# mainboard_motor_v1_3.net
KiCad netlist of a schematic drawn in Altium Designer
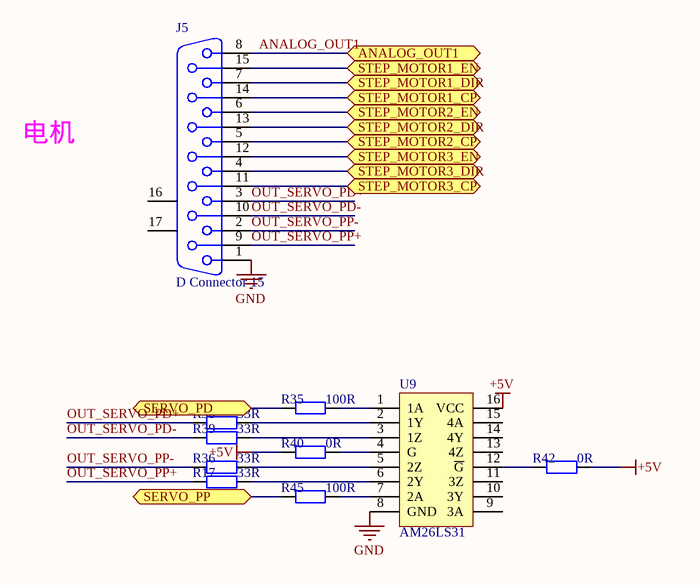
[diagram p0: mainboard_motor.v1.3.SchDoc]

(export (version "E")
  (design (tool "Eeschema 10.0.6"))
  (components
    (comp (ref "J5")
      (value "D Connector 15")
      (footprint "DSUB1.385-2H15")
      (description "Receptacle Assembly, 15 Position, Right Angle")
      (fields (field (name "PUBLISHER") "Altium Limited"))
      (libsource (lib "Miscellaneous Connectors") (part "D Connector 15"))
    )
    (comp (ref "R17")
      (value "33R")
      (footprint "0805")
      (description "Resistor")
      (fields (field (name "PUBLISHER") "Altium Limited"))
      (libsource (lib "TIAN's Schlib") (part "Res2"))
    )
    (comp (ref "R35")
      (value "100R")
      (footprint "0805")
      (description "Resistor")
      (fields (field (name "PUBLISHER") "Altium Limited"))
      (libsource (lib "TIAN's Schlib") (part "Res2"))
    )
    (comp (ref "R36")
      (value "33R")
      (footprint "0805")
      (description "Resistor")
      (fields (field (name "PUBLISHER") "Altium Limited"))
      (libsource (lib "TIAN's Schlib") (part "Res2"))
    )
    (comp (ref "R38")
      (value "33R")
      (footprint "0805")
      (description "Resistor")
      (fields (field (name "PUBLISHER") "Altium Limited"))
      (libsource (lib "TIAN's Schlib") (part "Res2"))
    )
    (comp (ref "R39")
      (value "33R")
      (footprint "0805")
      (description "Resistor")
      (fields (field (name "PUBLISHER") "Altium Limited"))
      (libsource (lib "TIAN's Schlib") (part "Res2"))
    )
    (comp (ref "R40")
      (value "0R")
      (footprint "0805")
      (description "Resistor")
      (fields (field (name "PUBLISHER") "Altium Limited"))
      (libsource (lib "TIAN's Schlib") (part "Res2"))
    )
    (comp (ref "R42")
      (value "0R")
      (footprint "0805")
      (description "Resistor")
      (fields (field (name "PUBLISHER") "Altium Limited"))
      (libsource (lib "TIAN's Schlib") (part "Res2"))
    )
    (comp (ref "R45")
      (value "100R")
      (footprint "0805")
      (description "Resistor")
      (fields (field (name "PUBLISHER") "Altium Limited"))
      (libsource (lib "TIAN's Schlib") (part "Res2"))
    )
    (comp (ref "U9") (value "AM26LS31") (footprint "SO-16") (libsource (lib "Chip") (part "AM26LS31")))
  )
  (nets
    (net (code "1") (name "+5V") (class "Default")
      (node (ref "R40") (pin "2") (pinfunction "2_2") (pintype "passive"))
      (node (ref "R42") (pin "1") (pinfunction "1_1") (pintype "passive"))
      (node (ref "U9") (pin "16") (pinfunction "VCC_16") (pintype "passive"))
    )
    (net (code "2") (name "/ANALOG_OUT1") (class "Default")
      (node (ref "J5") (pin "8") (pinfunction "8_8") (pintype "passive"))
    )
    (net (code "3") (name "/OUT_SERVO_PD+") (class "Default")
      (node (ref "J5") (pin "3") (pinfunction "3_3") (pintype "passive"))
      (node (ref "R38") (pin "2") (pinfunction "2_2") (pintype "passive"))
    )
    (net (code "4") (name "/OUT_SERVO_PD-") (class "Default")
      (node (ref "J5") (pin "10") (pinfunction "10_10") (pintype "passive"))
      (node (ref "R39") (pin "2") (pinfunction "2_2") (pintype "passive"))
    )
    (net (code "5") (name "/OUT_SERVO_PP+") (class "Default")
      (node (ref "J5") (pin "9") (pinfunction "9_9") (pintype "passive"))
      (node (ref "R17") (pin "2") (pinfunction "2_2") (pintype "passive"))
    )
    (net (code "6") (name "/OUT_SERVO_PP-") (class "Default")
      (node (ref "J5") (pin "2") (pinfunction "2_2") (pintype "passive"))
      (node (ref "R36") (pin "2") (pinfunction "2_2") (pintype "passive"))
    )
    (net (code "7") (name "/SERVO_PD") (class "Default")
      (node (ref "R35") (pin "2") (pinfunction "2_2") (pintype "passive"))
    )
    (net (code "8") (name "/SERVO_PP") (class "Default")
      (node (ref "R45") (pin "2") (pinfunction "2_2") (pintype "passive"))
    )
    (net (code "9") (name "/STEP_MOTOR1_CP") (class "Default")
      (node (ref "J5") (pin "14") (pinfunction "14_14") (pintype "passive"))
    )
    (net (code "10") (name "/STEP_MOTOR1_DIR") (class "Default")
      (node (ref "J5") (pin "7") (pinfunction "7_7") (pintype "passive"))
    )
    (net (code "11") (name "/STEP_MOTOR1_EN") (class "Default")
      (node (ref "J5") (pin "15") (pinfunction "15_15") (pintype "passive"))
    )
    (net (code "12") (name "/STEP_MOTOR2_CP") (class "Default")
      (node (ref "J5") (pin "5") (pinfunction "5_5") (pintype "passive"))
    )
    (net (code "13") (name "/STEP_MOTOR2_DIR") (class "Default")
      (node (ref "J5") (pin "13") (pinfunction "13_13") (pintype "passive"))
    )
    (net (code "14") (name "/STEP_MOTOR2_EN") (class "Default")
      (node (ref "J5") (pin "6") (pinfunction "6_6") (pintype "passive"))
    )
    (net (code "15") (name "/STEP_MOTOR3_CP") (class "Default")
      (node (ref "J5") (pin "11") (pinfunction "11_11") (pintype "passive"))
    )
    (net (code "16") (name "/STEP_MOTOR3_DIR") (class "Default")
      (node (ref "J5") (pin "4") (pinfunction "4_4") (pintype "passive"))
    )
    (net (code "17") (name "/STEP_MOTOR3_EN") (class "Default")
      (node (ref "J5") (pin "12") (pinfunction "12_12") (pintype "passive"))
    )
    (net (code "18") (name "GND") (class "Default")
      (node (ref "J5") (pin "1") (pinfunction "1_1") (pintype "passive"))
      (node (ref "U9") (pin "8") (pinfunction "GND_8") (pintype "passive"))
    )
    (net (code "19") (name "Net-(U9-1A)") (class "Default")
      (node (ref "R35") (pin "1") (pinfunction "1_1") (pintype "passive"))
      (node (ref "U9") (pin "1") (pinfunction "1A_1") (pintype "passive"))
    )
    (net (code "20") (name "Net-(U9-1Y)") (class "Default")
      (node (ref "R38") (pin "1") (pinfunction "1_1") (pintype "passive"))
      (node (ref "U9") (pin "2") (pinfunction "1Y_2") (pintype "passive"))
    )
    (net (code "21") (name "Net-(U9-1Z)") (class "Default")
      (node (ref "R39") (pin "1") (pinfunction "1_1") (pintype "passive"))
      (node (ref "U9") (pin "3") (pinfunction "1Z_3") (pintype "passive"))
    )
    (net (code "22") (name "Net-(U9-2A)") (class "Default")
      (node (ref "R45") (pin "1") (pinfunction "1_1") (pintype "passive"))
      (node (ref "U9") (pin "7") (pinfunction "2A_7") (pintype "passive"))
    )
    (net (code "23") (name "Net-(U9-2Y)") (class "Default")
      (node (ref "R17") (pin "1") (pinfunction "1_1") (pintype "passive"))
      (node (ref "U9") (pin "6") (pinfunction "2Y_6") (pintype "passive"))
    )
    (net (code "24") (name "Net-(U9-2Z)") (class "Default")
      (node (ref "R36") (pin "1") (pinfunction "1_1") (pintype "passive"))
      (node (ref "U9") (pin "5") (pinfunction "2Z_5") (pintype "passive"))
    )
    (net (code "25") (name "Net-(U9-G)") (class "Default")
      (node (ref "R40") (pin "1") (pinfunction "1_1") (pintype "passive"))
      (node (ref "U9") (pin "4") (pinfunction "G_4") (pintype "passive"))
    )
    (net (code "26") (name "Net-(U9-~{G})") (class "Default")
      (node (ref "R42") (pin "2") (pinfunction "2_2") (pintype "passive"))
      (node (ref "U9") (pin "12") (pinfunction "~{G}_12") (pintype "passive"))
    )
    (net (code "27") (name "unconnected-(J5-MH1-Pad16)") (class "Default")
      (node (ref "J5") (pin "16") (pinfunction "MH1_16") (pintype "passive"))
    )
    (net (code "28") (name "unconnected-(J5-MH2-Pad17)") (class "Default")
      (node (ref "J5") (pin "17") (pinfunction "MH2_17") (pintype "passive"))
    )
    (net (code "29") (name "unconnected-(U9-3A-Pad9)") (class "Default")
      (node (ref "U9") (pin "9") (pinfunction "3A_9") (pintype "passive"))
    )
    (net (code "30") (name "unconnected-(U9-3Y-Pad10)") (class "Default")
      (node (ref "U9") (pin "10") (pinfunction "3Y_10") (pintype "passive"))
    )
    (net (code "31") (name "unconnected-(U9-3Z-Pad11)") (class "Default")
      (node (ref "U9") (pin "11") (pinfunction "3Z_11") (pintype "passive"))
    )
    (net (code "32") (name "unconnected-(U9-4A-Pad15)") (class "Default")
      (node (ref "U9") (pin "15") (pinfunction "4A_15") (pintype "passive"))
    )
    (net (code "33") (name "unconnected-(U9-4Y-Pad14)") (class "Default")
      (node (ref "U9") (pin "14") (pinfunction "4Y_14") (pintype "passive"))
    )
    (net (code "34") (name "unconnected-(U9-4Z-Pad13)") (class "Default")
      (node (ref "U9") (pin "13") (pinfunction "4Z_13") (pintype "passive"))
    )
  )
)
